# tinkertechLED.net
KiCad netlist of a schematic drawn in EAGLE
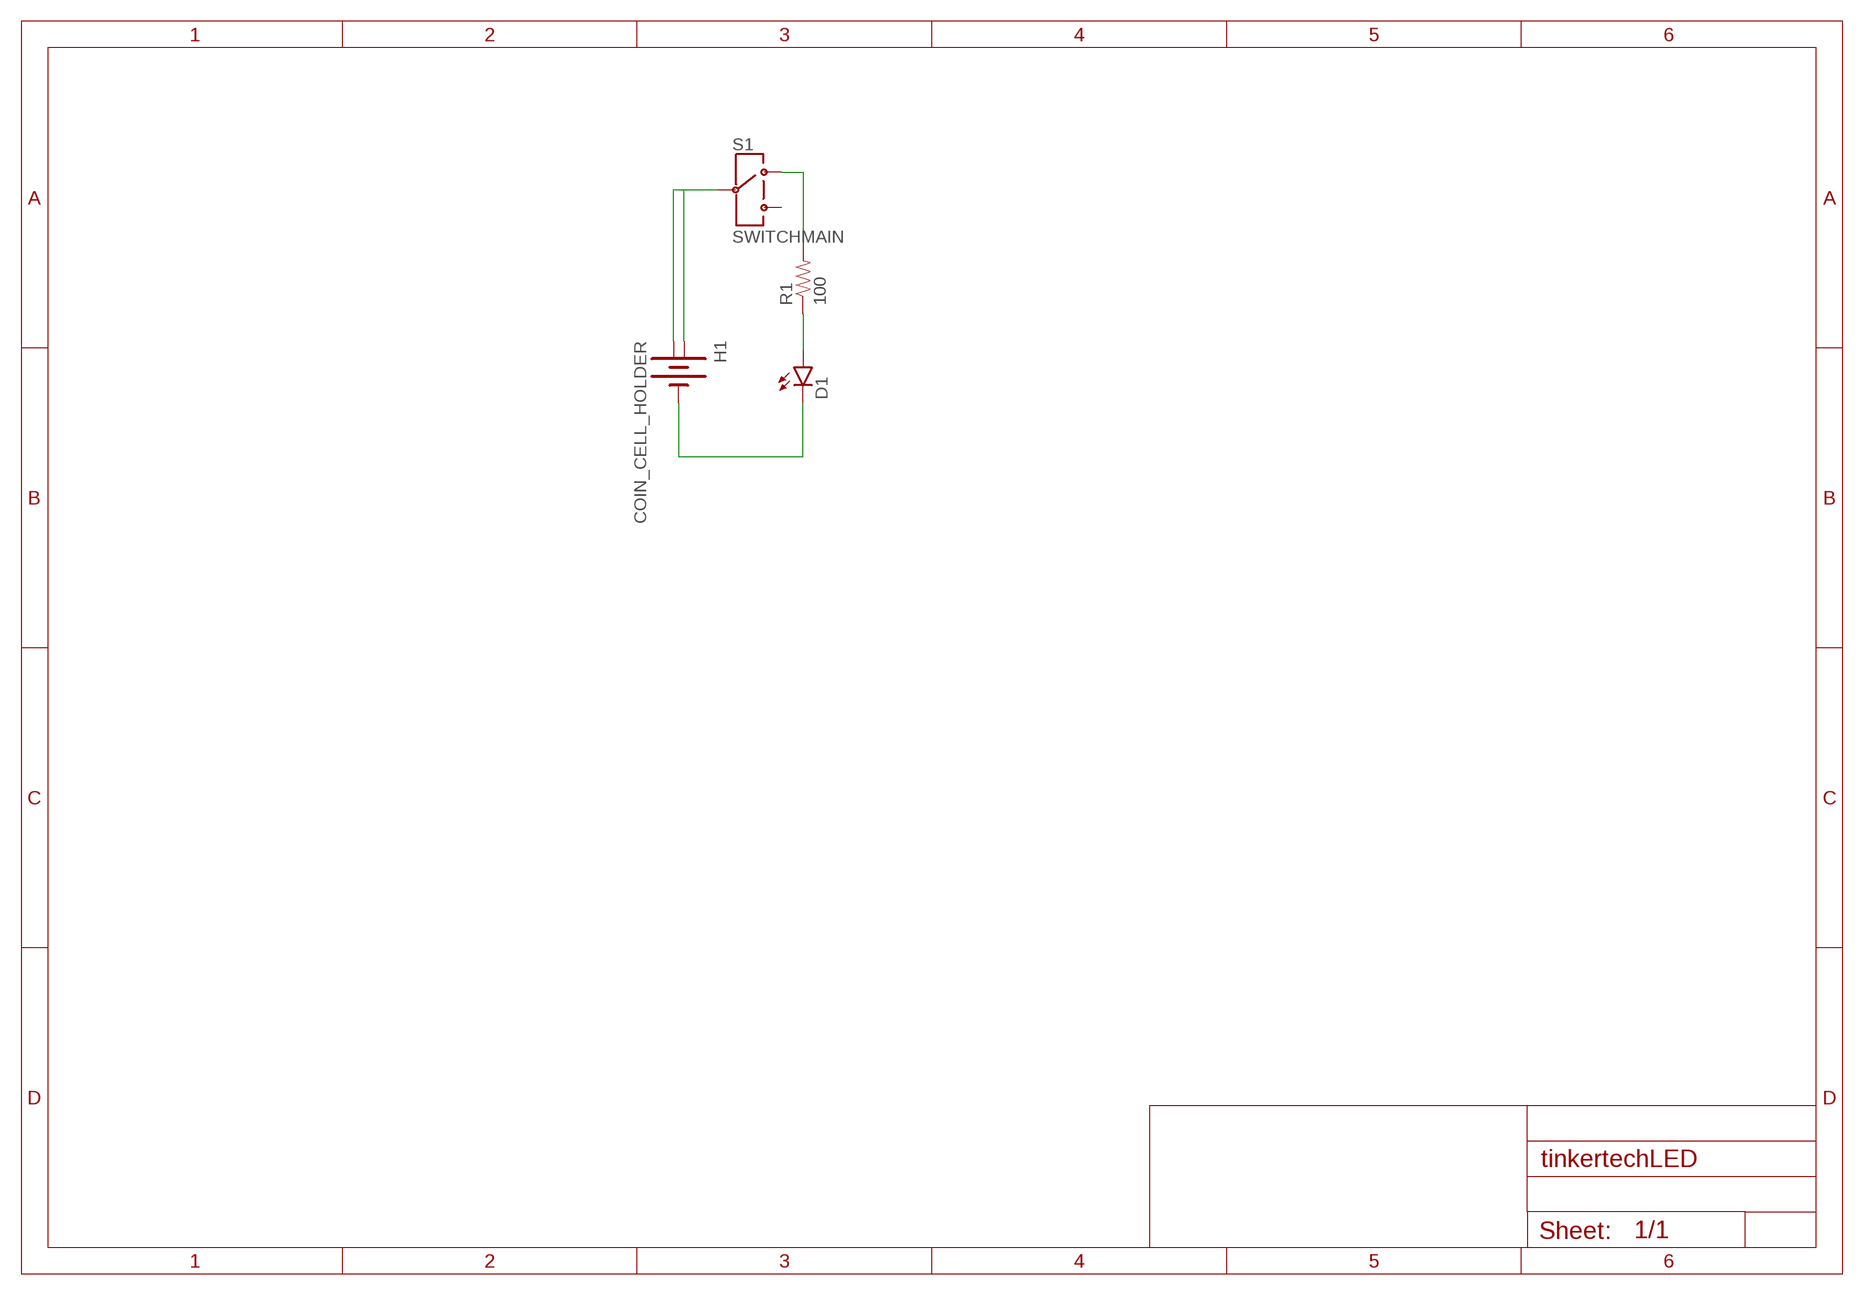
[diagram p0: schematic, sheet 1]

(export (version "E")
  (design (tool "Eeschema 10.0.6"))
  (components
    (comp (ref "D1")
      (value "LED5MM")
      (footprint "eagle-import:LED5MM")
      (libsource (lib "eagle-import") (part "LED5MM"))
    )
    (comp (ref "H1")
      (value "COIN_CELL_HOLDER")
      (footprint "eagle-import:COIN_CELL_HOLDER")
      (libsource (lib "eagle-import") (part "COIN_CELL_HOLDER"))
    )
    (comp (ref "R1")
      (value "100")
      (footprint "eagle-import:AXIAL-0.3-KIT")
      (libsource (lib "eagle-import") (part "RESISTORKIT"))
    )
    (comp (ref "S1")
      (value "SWITCHMAIN")
      (footprint "eagle-import:SWITCH")
      (libsource (lib "eagle-import") (part "SWITCHMAIN"))
    )
  )
  (nets
    (net (code "1") (name "Net-(D1-C)") (class "Default")
      (node (ref "D1") (pin "K") (pinfunction "C_K") (pintype "passive"))
      (node (ref "H1") (pin "P$1") (pinfunction "-_P$1") (pintype "power_in"))
    )
    (net (code "2") (name "Net-(H1-+)") (class "Default")
      (node (ref "H1") (pin "P$2") (pinfunction "+_P$2") (pintype "power_in"))
      (node (ref "H1") (pin "P$3") (pinfunction "++_P$3") (pintype "power_in"))
      (node (ref "S1") (pin "P$2") (pinfunction "C_P$2") (pintype "bidirectional"))
    )
    (net (code "3") (name "Net-(R1-1)") (class "Default")
      (node (ref "D1") (pin "A") (pinfunction "A_A") (pintype "passive"))
      (node (ref "R1") (pin "P$1") (pinfunction "1_P$1") (pintype "passive"))
    )
    (net (code "4") (name "Net-(R1-2)") (class "Default")
      (node (ref "R1") (pin "P$2") (pinfunction "2_P$2") (pintype "passive"))
      (node (ref "S1") (pin "P$1") (pinfunction "1_P$1") (pintype "bidirectional"))
    )
    (net (code "5") (name "unconnected-(S1-2-PadP$3)") (class "Default")
      (node (ref "S1") (pin "P$3") (pinfunction "2_P$3") (pintype "bidirectional"))
    )
  )
)
